# keyer.net
KiCad netlist of a schematic drawn in EAGLE
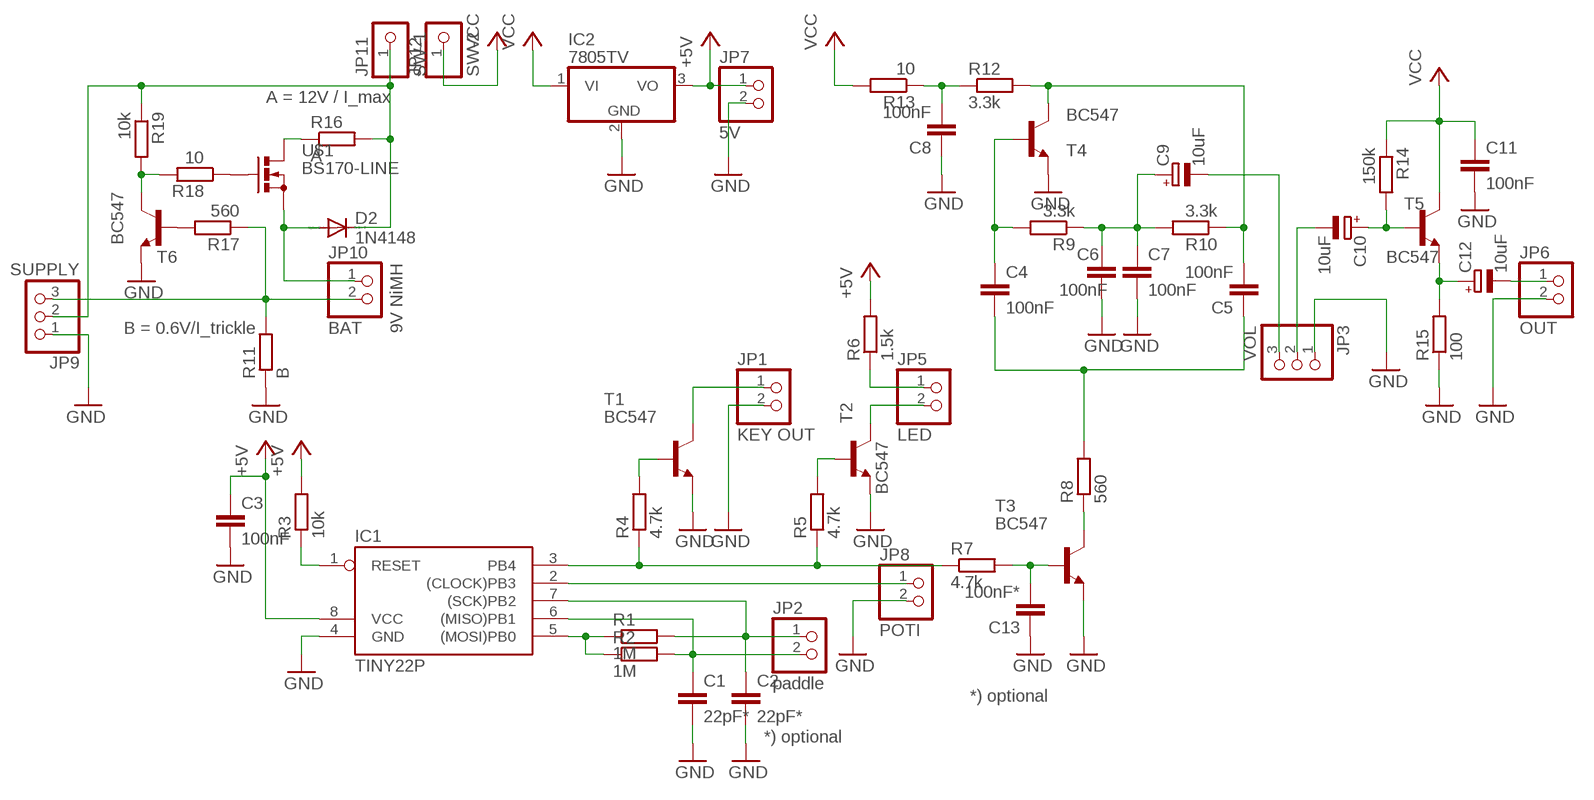
[diagram p0: schematic, sheet 1]

(export (version "E")
  (design (tool "Eeschema 10.0.6"))
  (components
    (comp (ref "C1")
      (value "22pF*")
      (footprint "eagle-import:C050-025X075")
      (libsource (lib "eagle-import") (part "C-EU050-025X075"))
    )
    (comp (ref "C2")
      (value "22pF*")
      (footprint "eagle-import:C050-025X075")
      (libsource (lib "eagle-import") (part "C-EU050-025X075"))
    )
    (comp (ref "C3")
      (value "100nF")
      (footprint "eagle-import:C075-032X103")
      (libsource (lib "eagle-import") (part "C-EU075-032X103"))
    )
    (comp (ref "C4")
      (value "100nF")
      (footprint "eagle-import:C025-025X050")
      (libsource (lib "eagle-import") (part "C-EU025-025X050"))
    )
    (comp (ref "C5")
      (value "100nF")
      (footprint "eagle-import:C025-025X050")
      (libsource (lib "eagle-import") (part "C-EU025-025X050"))
    )
    (comp (ref "C6")
      (value "100nF")
      (footprint "eagle-import:C025-025X050")
      (libsource (lib "eagle-import") (part "C-EU025-025X050"))
    )
    (comp (ref "C7")
      (value "100nF")
      (footprint "eagle-import:C025-025X050")
      (libsource (lib "eagle-import") (part "C-EU025-025X050"))
    )
    (comp (ref "C8")
      (value "100nF")
      (footprint "eagle-import:C025-025X050")
      (libsource (lib "eagle-import") (part "C-EU025-025X050"))
    )
    (comp (ref "C9")
      (value "10uF")
      (footprint "eagle-import:E2,5-6")
      (libsource (lib "eagle-import") (part "CPOL-EUE2.5-6"))
    )
    (comp (ref "C10")
      (value "10uF")
      (footprint "eagle-import:E2,5-6")
      (libsource (lib "eagle-import") (part "CPOL-EUE2.5-6"))
    )
    (comp (ref "C11")
      (value "100nF")
      (footprint "eagle-import:C025-025X050")
      (libsource (lib "eagle-import") (part "C-EU025-025X050"))
    )
    (comp (ref "C12")
      (value "10uF")
      (footprint "eagle-import:E2,5-6")
      (libsource (lib "eagle-import") (part "CPOL-EUE2.5-6"))
    )
    (comp (ref "C13")
      (value "100nF*")
      (footprint "eagle-import:C025-025X050")
      (libsource (lib "eagle-import") (part "C-EU025-025X050"))
    )
    (comp (ref "D2")
      (value "1N4148")
      (footprint "eagle-import:D-2.5")
      (libsource (lib "eagle-import") (part "DIODE-D-2.5"))
    )
    (comp (ref "IC1")
      (value "TINY22P")
      (footprint "eagle-import:DIL08")
      (libsource (lib "eagle-import") (part "TINY22P"))
    )
    (comp (ref "IC2")
      (value "7805TV")
      (footprint "eagle-import:TO220V")
      (libsource (lib "eagle-import") (part "78TV05"))
    )
    (comp (ref "JP1")
      (value "KEY OUT")
      (footprint "eagle-import:1X02")
      (libsource (lib "eagle-import") (part "PINHD-1X2"))
    )
    (comp (ref "JP2")
      (value "paddle")
      (footprint "eagle-import:1X02")
      (libsource (lib "eagle-import") (part "PINHD-1X2"))
    )
    (comp (ref "JP3")
      (value "VOL")
      (footprint "eagle-import:1X03")
      (libsource (lib "eagle-import") (part "PINHD-1X3"))
    )
    (comp (ref "JP5")
      (value "LED")
      (footprint "eagle-import:1X02")
      (libsource (lib "eagle-import") (part "PINHD-1X2"))
    )
    (comp (ref "JP6")
      (value "OUT")
      (footprint "eagle-import:1X02")
      (libsource (lib "eagle-import") (part "PINHD-1X2"))
    )
    (comp (ref "JP7")
      (value "5V")
      (footprint "eagle-import:1X02")
      (libsource (lib "eagle-import") (part "PINHD-1X2"))
    )
    (comp (ref "JP8")
      (value "POTI")
      (footprint "eagle-import:1X02")
      (libsource (lib "eagle-import") (part "PINHD-1X2"))
    )
    (comp (ref "JP9")
      (value "SUPPLY")
      (footprint "eagle-import:1X03")
      (libsource (lib "eagle-import") (part "PINHD-1X3"))
    )
    (comp (ref "JP10")
      (value "BAT")
      (footprint "eagle-import:1X02")
      (libsource (lib "eagle-import") (part "PINHD-1X2"))
    )
    (comp (ref "JP11")
      (value "SW-1")
      (footprint "eagle-import:1X01")
      (libsource (lib "eagle-import") (part "PINHD-1X1"))
    )
    (comp (ref "JP12")
      (value "SW-2")
      (footprint "eagle-import:1X01")
      (libsource (lib "eagle-import") (part "PINHD-1X1"))
    )
    (comp (ref "R1")
      (value "1M")
      (footprint "eagle-import:0204_5")
      (libsource (lib "eagle-import") (part "R-EU_0204/5"))
    )
    (comp (ref "R2")
      (value "1M")
      (footprint "eagle-import:0204V")
      (libsource (lib "eagle-import") (part "R-EU_0204/2V"))
    )
    (comp (ref "R3")
      (value "10k")
      (footprint "eagle-import:0204_5")
      (libsource (lib "eagle-import") (part "R-EU_0204/5"))
    )
    (comp (ref "R4")
      (value "4.7k")
      (footprint "eagle-import:0204_5")
      (libsource (lib "eagle-import") (part "R-EU_0204/5"))
    )
    (comp (ref "R5")
      (value "4.7k")
      (footprint "eagle-import:0204_5")
      (libsource (lib "eagle-import") (part "R-EU_0204/5"))
    )
    (comp (ref "R6")
      (value "1.5k")
      (footprint "eagle-import:0204_5")
      (libsource (lib "eagle-import") (part "R-EU_0204/5"))
    )
    (comp (ref "R7")
      (value "4.7k")
      (footprint "eagle-import:0204_5")
      (libsource (lib "eagle-import") (part "R-EU_0204/5"))
    )
    (comp (ref "R8")
      (value "560")
      (footprint "eagle-import:0204V")
      (libsource (lib "eagle-import") (part "R-EU_0204/2V"))
    )
    (comp (ref "R9")
      (value "3.3k")
      (footprint "eagle-import:0204_5")
      (libsource (lib "eagle-import") (part "R-EU_0204/5"))
    )
    (comp (ref "R10")
      (value "3.3k")
      (footprint "eagle-import:0204_7")
      (libsource (lib "eagle-import") (part "R-EU_0204/7"))
    )
    (comp (ref "R11")
      (value "B")
      (footprint "eagle-import:0204_5")
      (libsource (lib "eagle-import") (part "R-EU_0204/5"))
    )
    (comp (ref "R12")
      (value "3.3k")
      (footprint "eagle-import:0204_5")
      (libsource (lib "eagle-import") (part "R-EU_0204/5"))
    )
    (comp (ref "R13")
      (value "10")
      (footprint "eagle-import:0204V")
      (libsource (lib "eagle-import") (part "R-EU_0204/2V"))
    )
    (comp (ref "R14")
      (value "150k")
      (footprint "eagle-import:0204V")
      (libsource (lib "eagle-import") (part "R-EU_0204/2V"))
    )
    (comp (ref "R15")
      (value "100")
      (footprint "eagle-import:0204_7")
      (libsource (lib "eagle-import") (part "R-EU_0204/7"))
    )
    (comp (ref "R16")
      (value "A")
      (footprint "eagle-import:0204V")
      (libsource (lib "eagle-import") (part "R-EU_0204/2V"))
    )
    (comp (ref "R17")
      (value "560")
      (footprint "eagle-import:0204_5")
      (libsource (lib "eagle-import") (part "R-EU_0204/5"))
    )
    (comp (ref "R18")
      (value "10")
      (footprint "eagle-import:0204_5")
      (libsource (lib "eagle-import") (part "R-EU_0204/5"))
    )
    (comp (ref "R19")
      (value "10k")
      (footprint "eagle-import:0204V")
      (libsource (lib "eagle-import") (part "R-EU_0204/2V"))
    )
    (comp (ref "T1")
      (value "BC547")
      (footprint "eagle-import:TO92-CBE")
      (libsource (lib "eagle-import") (part "-NPN-TO92-CBE"))
    )
    (comp (ref "T2")
      (value "BC547")
      (footprint "eagle-import:TO92-CBE")
      (libsource (lib "eagle-import") (part "-NPN-TO92-CBE"))
    )
    (comp (ref "T3")
      (value "BC547")
      (footprint "eagle-import:TO92-CBE")
      (libsource (lib "eagle-import") (part "-NPN-TO92-CBE"))
    )
    (comp (ref "T4")
      (value "BC547")
      (footprint "eagle-import:TO92-CBE")
      (libsource (lib "eagle-import") (part "-NPN-TO92-CBE"))
    )
    (comp (ref "T5")
      (value "BC547")
      (footprint "eagle-import:TO92-CBE")
      (libsource (lib "eagle-import") (part "-NPN-TO92-CBE"))
    )
    (comp (ref "T6")
      (value "BC547")
      (footprint "eagle-import:TO92-CBE")
      (libsource (lib "eagle-import") (part "-NPN-TO92-CBE"))
    )
    (comp (ref "U$1")
      (value "BS170-LINE")
      (footprint "eagle-import:TO92-LINE")
      (libsource (lib "eagle-import") (part "BS170-LINE"))
    )
  )
  (nets
    (net (code "1") (name "+5V") (class "Default")
      (node (ref "C3") (pin "1") (pinfunction "1_1") (pintype "passive"))
      (node (ref "IC1") (pin "8") (pinfunction "VCC_8") (pintype "power_in"))
      (node (ref "IC2") (pin "3") (pinfunction "VO_3") (pintype "passive"))
      (node (ref "JP7") (pin "1") (pinfunction "1_1") (pintype "passive"))
      (node (ref "R3") (pin "2") (pinfunction "2_2") (pintype "passive"))
      (node (ref "R6") (pin "2") (pinfunction "2_2") (pintype "passive"))
    )
    (net (code "2") (name "GND") (class "Default")
      (node (ref "C1") (pin "2") (pinfunction "2_2") (pintype "passive"))
      (node (ref "C11") (pin "2") (pinfunction "2_2") (pintype "passive"))
      (node (ref "C13") (pin "1") (pinfunction "1_1") (pintype "passive"))
      (node (ref "C2") (pin "2") (pinfunction "2_2") (pintype "passive"))
      (node (ref "C3") (pin "2") (pinfunction "2_2") (pintype "passive"))
      (node (ref "C6") (pin "2") (pinfunction "2_2") (pintype "passive"))
      (node (ref "C7") (pin "2") (pinfunction "2_2") (pintype "passive"))
      (node (ref "C8") (pin "1") (pinfunction "1_1") (pintype "passive"))
      (node (ref "IC1") (pin "4") (pinfunction "GND_4") (pintype "power_in"))
      (node (ref "IC2") (pin "2") (pinfunction "GND_2") (pintype "passive"))
      (node (ref "JP1") (pin "2") (pinfunction "2_2") (pintype "passive"))
      (node (ref "JP3") (pin "1") (pinfunction "1_1") (pintype "passive"))
      (node (ref "JP6") (pin "2") (pinfunction "2_2") (pintype "passive"))
      (node (ref "JP7") (pin "2") (pinfunction "2_2") (pintype "passive"))
      (node (ref "JP8") (pin "2") (pinfunction "2_2") (pintype "passive"))
      (node (ref "JP9") (pin "1") (pinfunction "1_1") (pintype "passive"))
      (node (ref "R11") (pin "1") (pinfunction "1_1") (pintype "passive"))
      (node (ref "R15") (pin "1") (pinfunction "1_1") (pintype "passive"))
      (node (ref "T1") (pin "E") (pinfunction "E_E") (pintype "passive"))
      (node (ref "T2") (pin "E") (pinfunction "E_E") (pintype "passive"))
      (node (ref "T3") (pin "E") (pinfunction "E_E") (pintype "passive"))
      (node (ref "T4") (pin "E") (pinfunction "E_E") (pintype "passive"))
      (node (ref "T6") (pin "E") (pinfunction "E_E") (pintype "passive"))
    )
    (net (code "3") (name "Net-(C4-Pad1)") (class "Default")
      (node (ref "C4") (pin "1") (pinfunction "1_1") (pintype "passive"))
      (node (ref "R9") (pin "2") (pinfunction "2_2") (pintype "passive"))
      (node (ref "T4") (pin "B") (pinfunction "B_B") (pintype "passive"))
    )
    (net (code "4") (name "Net-(C4-Pad2)") (class "Default")
      (node (ref "C4") (pin "2") (pinfunction "2_2") (pintype "passive"))
      (node (ref "C5") (pin "1") (pinfunction "1_1") (pintype "passive"))
      (node (ref "R8") (pin "2") (pinfunction "2_2") (pintype "passive"))
    )
    (net (code "5") (name "Net-(C5-Pad2)") (class "Default")
      (node (ref "C5") (pin "2") (pinfunction "2_2") (pintype "passive"))
      (node (ref "R10") (pin "1") (pinfunction "1_1") (pintype "passive"))
      (node (ref "R12") (pin "2") (pinfunction "2_2") (pintype "passive"))
      (node (ref "T4") (pin "C") (pinfunction "C_C") (pintype "passive"))
    )
    (net (code "6") (name "Net-(C6-Pad1)") (class "Default")
      (node (ref "C6") (pin "1") (pinfunction "1_1") (pintype "passive"))
      (node (ref "C7") (pin "1") (pinfunction "1_1") (pintype "passive"))
      (node (ref "C9") (pin "+") (pinfunction "+_+") (pintype "passive"))
      (node (ref "R10") (pin "2") (pinfunction "2_2") (pintype "passive"))
      (node (ref "R9") (pin "1") (pinfunction "1_1") (pintype "passive"))
    )
    (net (code "7") (name "Net-(C8-Pad2)") (class "Default")
      (node (ref "C8") (pin "2") (pinfunction "2_2") (pintype "passive"))
      (node (ref "R12") (pin "1") (pinfunction "1_1") (pintype "passive"))
      (node (ref "R13") (pin "1") (pinfunction "1_1") (pintype "passive"))
    )
    (net (code "8") (name "Net-(C9-Pad-)") (class "Default")
      (node (ref "C9") (pin "-") (pinfunction "-_-") (pintype "passive"))
      (node (ref "JP3") (pin "3") (pinfunction "3_3") (pintype "passive"))
    )
    (net (code "9") (name "Net-(C10-Pad+)") (class "Default")
      (node (ref "C10") (pin "+") (pinfunction "+_+") (pintype "passive"))
      (node (ref "R14") (pin "2") (pinfunction "2_2") (pintype "passive"))
      (node (ref "T5") (pin "B") (pinfunction "B_B") (pintype "passive"))
    )
    (net (code "10") (name "Net-(C10-Pad-)") (class "Default")
      (node (ref "C10") (pin "-") (pinfunction "-_-") (pintype "passive"))
      (node (ref "JP3") (pin "2") (pinfunction "2_2") (pintype "passive"))
    )
    (net (code "11") (name "Net-(C12-Pad+)") (class "Default")
      (node (ref "C12") (pin "+") (pinfunction "+_+") (pintype "passive"))
      (node (ref "R15") (pin "2") (pinfunction "2_2") (pintype "passive"))
      (node (ref "T5") (pin "E") (pinfunction "E_E") (pintype "passive"))
    )
    (net (code "12") (name "Net-(C12-Pad-)") (class "Default")
      (node (ref "C12") (pin "-") (pinfunction "-_-") (pintype "passive"))
      (node (ref "JP6") (pin "1") (pinfunction "1_1") (pintype "passive"))
    )
    (net (code "13") (name "Net-(C13-Pad2)") (class "Default")
      (node (ref "C13") (pin "2") (pinfunction "2_2") (pintype "passive"))
      (node (ref "R7") (pin "2") (pinfunction "2_2") (pintype "passive"))
      (node (ref "T3") (pin "B") (pinfunction "B_B") (pintype "passive"))
    )
    (net (code "14") (name "Net-(D2-PadC)") (class "Default")
      (node (ref "D2") (pin "C") (pinfunction "C_C") (pintype "passive"))
      (node (ref "JP11") (pin "1") (pinfunction "1_1") (pintype "passive"))
      (node (ref "JP9") (pin "2") (pinfunction "2_2") (pintype "passive"))
      (node (ref "R16") (pin "2") (pinfunction "2_2") (pintype "passive"))
      (node (ref "R19") (pin "1") (pinfunction "1_1") (pintype "passive"))
    )
    (net (code "15") (name "Net-(IC1-(CLOCK)PB3)") (class "Default")
      (node (ref "IC1") (pin "2") (pinfunction "(CLOCK)PB3_2") (pintype "bidirectional"))
      (node (ref "JP8") (pin "1") (pinfunction "1_1") (pintype "passive"))
    )
    (net (code "16") (name "Net-(IC1-(MISO)PB1)") (class "Default")
      (node (ref "C1") (pin "1") (pinfunction "1_1") (pintype "passive"))
      (node (ref "IC1") (pin "6") (pinfunction "(MISO)PB1_6") (pintype "bidirectional"))
      (node (ref "JP2") (pin "2") (pinfunction "2_2") (pintype "passive"))
      (node (ref "R2") (pin "2") (pinfunction "2_2") (pintype "passive"))
    )
    (net (code "17") (name "Net-(IC1-(MOSI)PB0)") (class "Default")
      (node (ref "IC1") (pin "5") (pinfunction "(MOSI)PB0_5") (pintype "bidirectional"))
      (node (ref "R1") (pin "1") (pinfunction "1_1") (pintype "passive"))
      (node (ref "R2") (pin "1") (pinfunction "1_1") (pintype "passive"))
    )
    (net (code "18") (name "Net-(IC1-(SCK)PB2)") (class "Default")
      (node (ref "C2") (pin "1") (pinfunction "1_1") (pintype "passive"))
      (node (ref "IC1") (pin "7") (pinfunction "(SCK)PB2_7") (pintype "bidirectional"))
      (node (ref "JP2") (pin "1") (pinfunction "1_1") (pintype "passive"))
      (node (ref "R1") (pin "2") (pinfunction "2_2") (pintype "passive"))
    )
    (net (code "19") (name "Net-(IC1-PB4)") (class "Default")
      (node (ref "IC1") (pin "3") (pinfunction "PB4_3") (pintype "bidirectional"))
      (node (ref "R4") (pin "1") (pinfunction "1_1") (pintype "passive"))
      (node (ref "R5") (pin "1") (pinfunction "1_1") (pintype "passive"))
      (node (ref "R7") (pin "1") (pinfunction "1_1") (pintype "passive"))
    )
    (net (code "20") (name "Net-(IC1-RESET)") (class "Default")
      (node (ref "IC1") (pin "1") (pinfunction "RESET_1") (pintype "input"))
      (node (ref "R3") (pin "1") (pinfunction "1_1") (pintype "passive"))
    )
    (net (code "21") (name "Net-(JP1-Pad1)") (class "Default")
      (node (ref "JP1") (pin "1") (pinfunction "1_1") (pintype "passive"))
      (node (ref "T1") (pin "C") (pinfunction "C_C") (pintype "passive"))
    )
    (net (code "22") (name "Net-(JP5-Pad1)") (class "Default")
      (node (ref "JP5") (pin "1") (pinfunction "1_1") (pintype "passive"))
      (node (ref "R6") (pin "1") (pinfunction "1_1") (pintype "passive"))
    )
    (net (code "23") (name "Net-(JP5-Pad2)") (class "Default")
      (node (ref "JP5") (pin "2") (pinfunction "2_2") (pintype "passive"))
      (node (ref "T2") (pin "C") (pinfunction "C_C") (pintype "passive"))
    )
    (net (code "24") (name "Net-(JP10-Pad2)") (class "Default")
      (node (ref "JP10") (pin "2") (pinfunction "2_2") (pintype "passive"))
      (node (ref "JP9") (pin "3") (pinfunction "3_3") (pintype "passive"))
      (node (ref "R11") (pin "2") (pinfunction "2_2") (pintype "passive"))
      (node (ref "R17") (pin "1") (pinfunction "1_1") (pintype "passive"))
    )
    (net (code "25") (name "Net-(R4-Pad2)") (class "Default")
      (node (ref "R4") (pin "2") (pinfunction "2_2") (pintype "passive"))
      (node (ref "T1") (pin "B") (pinfunction "B_B") (pintype "passive"))
    )
    (net (code "26") (name "Net-(R5-Pad2)") (class "Default")
      (node (ref "R5") (pin "2") (pinfunction "2_2") (pintype "passive"))
      (node (ref "T2") (pin "B") (pinfunction "B_B") (pintype "passive"))
    )
    (net (code "27") (name "Net-(R8-Pad1)") (class "Default")
      (node (ref "R8") (pin "1") (pinfunction "1_1") (pintype "passive"))
      (node (ref "T3") (pin "C") (pinfunction "C_C") (pintype "passive"))
    )
    (net (code "28") (name "Net-(R17-Pad2)") (class "Default")
      (node (ref "R17") (pin "2") (pinfunction "2_2") (pintype "passive"))
      (node (ref "T6") (pin "B") (pinfunction "B_B") (pintype "passive"))
    )
    (net (code "29") (name "Net-(R18-Pad2)") (class "Default")
      (node (ref "R18") (pin "2") (pinfunction "2_2") (pintype "passive"))
      (node (ref "R19") (pin "2") (pinfunction "2_2") (pintype "passive"))
      (node (ref "T6") (pin "C") (pinfunction "C_C") (pintype "passive"))
    )
    (net (code "30") (name "Net-(U$1-D)") (class "Default")
      (node (ref "R16") (pin "1") (pinfunction "1_1") (pintype "passive"))
      (node (ref "U$1") (pin "3") (pinfunction "D_3") (pintype "passive"))
    )
    (net (code "31") (name "Net-(U$1-G)") (class "Default")
      (node (ref "R18") (pin "1") (pinfunction "1_1") (pintype "passive"))
      (node (ref "U$1") (pin "2") (pinfunction "G_2") (pintype "passive"))
    )
    (net (code "32") (name "Net-(U$1-S)") (class "Default")
      (node (ref "D2") (pin "A") (pinfunction "A_A") (pintype "passive"))
      (node (ref "JP10") (pin "1") (pinfunction "1_1") (pintype "passive"))
      (node (ref "U$1") (pin "1") (pinfunction "S_1") (pintype "passive"))
    )
    (net (code "33") (name "VCC") (class "Default")
      (node (ref "C11") (pin "1") (pinfunction "1_1") (pintype "passive"))
      (node (ref "IC2") (pin "1") (pinfunction "VI_1") (pintype "input"))
      (node (ref "JP12") (pin "1") (pinfunction "1_1") (pintype "passive"))
      (node (ref "R13") (pin "2") (pinfunction "2_2") (pintype "passive"))
      (node (ref "R14") (pin "1") (pinfunction "1_1") (pintype "passive"))
      (node (ref "T5") (pin "C") (pinfunction "C_C") (pintype "passive"))
    )
  )
)
